# Bracelet_v3.net
KiCad netlist of a schematic drawn in EAGLE
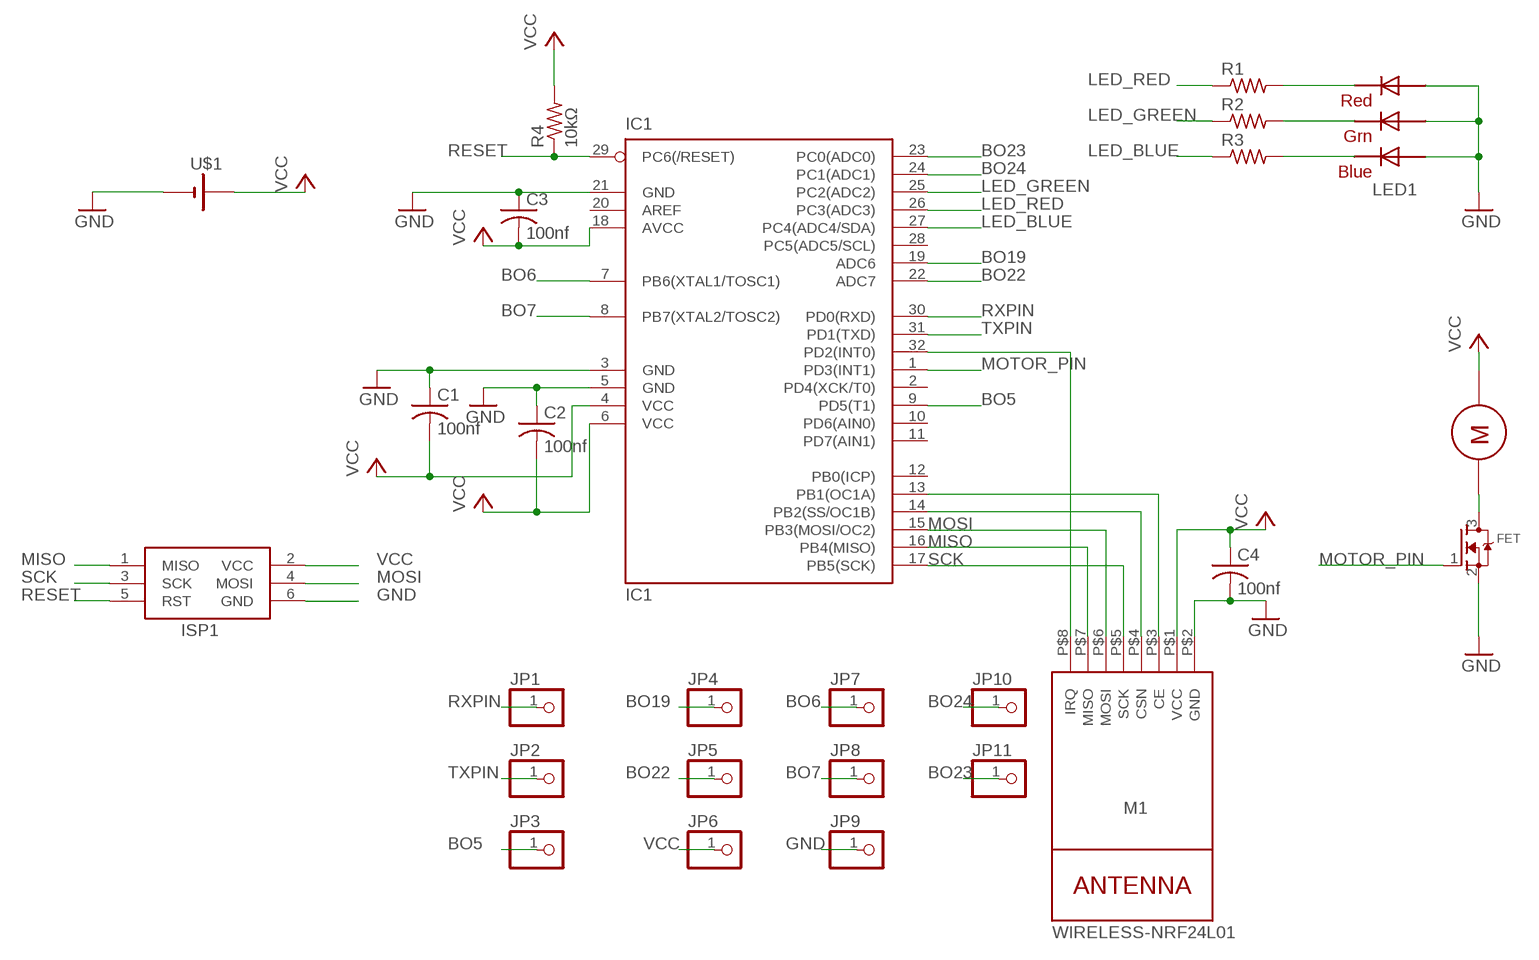
[diagram p0: schematic, sheet 1]

(export (version "E")
  (design (tool "Eeschema 10.0.6"))
  (components
    (comp (ref "C1")
      (value "100nf")
      (footprint "eagle-import:C0805")
      (libsource (lib "eagle-import") (part "resistor_C-USC0805"))
    )
    (comp (ref "C2")
      (value "100nf")
      (footprint "eagle-import:C0805")
      (libsource (lib "eagle-import") (part "C-USC0805"))
    )
    (comp (ref "C3")
      (value "100nf")
      (footprint "eagle-import:C0805")
      (libsource (lib "eagle-import") (part "resistor_C-USC0805"))
    )
    (comp (ref "C4")
      (value "100nf")
      (footprint "eagle-import:C0805")
      (libsource (lib "eagle-import") (part "C-USC0805"))
    )
    (comp (ref "FET")
      (value "MOSFET-NREFLOW")
      (footprint "eagle-import:SOT23")
      (libsource (lib "eagle-import") (part "MOSFET-NREFLOW"))
    )
    (comp (ref "IC1")
      (value "IC1")
      (footprint "eagle-import:TQFP32-08")
      (fields (field (name "MPN") "ATMEGA8-16AU"))
      (libsource (lib "eagle-import") (part "MEGA8-AI"))
    )
    (comp (ref "ISP1")
      (value "AVRISP-6")
      (footprint "eagle-import:AVRISP")
      (libsource (lib "eagle-import") (part "AVRISP-6"))
    )
    (comp (ref "JP1")
      (value "PINHD-1X1")
      (footprint "eagle-import:1X01")
      (libsource (lib "eagle-import") (part "PINHD-1X1"))
    )
    (comp (ref "JP2")
      (value "PINHD-1X1")
      (footprint "eagle-import:1X01")
      (libsource (lib "eagle-import") (part "PINHD-1X1"))
    )
    (comp (ref "JP3")
      (value "PINHD-1X1")
      (footprint "eagle-import:1X01")
      (libsource (lib "eagle-import") (part "PINHD-1X1"))
    )
    (comp (ref "JP4")
      (value "PINHD-1X1")
      (footprint "eagle-import:1X01")
      (libsource (lib "eagle-import") (part "PINHD-1X1"))
    )
    (comp (ref "JP5")
      (value "PINHD-1X1")
      (footprint "eagle-import:1X01")
      (libsource (lib "eagle-import") (part "PINHD-1X1"))
    )
    (comp (ref "JP6")
      (value "PINHD-1X1")
      (footprint "eagle-import:1X01")
      (libsource (lib "eagle-import") (part "PINHD-1X1"))
    )
    (comp (ref "JP7")
      (value "PINHD-1X1")
      (footprint "eagle-import:1X01")
      (libsource (lib "eagle-import") (part "PINHD-1X1"))
    )
    (comp (ref "JP8")
      (value "PINHD-1X1")
      (footprint "eagle-import:1X01")
      (libsource (lib "eagle-import") (part "PINHD-1X1"))
    )
    (comp (ref "JP9")
      (value "PINHD-1X1")
      (footprint "eagle-import:1X01")
      (libsource (lib "eagle-import") (part "PINHD-1X1"))
    )
    (comp (ref "JP10")
      (value "PINHD-1X1")
      (footprint "eagle-import:1X01")
      (libsource (lib "eagle-import") (part "PINHD-1X1"))
    )
    (comp (ref "JP11")
      (value "PINHD-1X1")
      (footprint "eagle-import:1X01")
      (libsource (lib "eagle-import") (part "PINHD-1X1"))
    )
    (comp (ref "LED1")
      (value "RGBLED5050")
      (footprint "eagle-import:RGBLED5050")
      (libsource (lib "eagle-import") (part "RGBLED5050"))
    )
    (comp (ref "M1")
      (value "WIRELESS-NRF24L01")
      (footprint "eagle-import:WIRELESS-NRF24L01")
      (libsource (lib "eagle-import") (part "WIRELESS-NRF24L01"))
    )
    (comp (ref "MOTOR")
      (value "Motor")
      (footprint "eagle-import:VIBRATING-MOTOR")
      (libsource (lib "eagle-import") (part "VIBRATING-MOTOR"))
    )
    (comp (ref "R1")
      (value "R-US_R0805")
      (footprint "eagle-import:R0805")
      (libsource (lib "eagle-import") (part "R-US_R0805"))
    )
    (comp (ref "R2")
      (value "R-US_R0805")
      (footprint "eagle-import:R0805")
      (libsource (lib "eagle-import") (part "R-US_R0805"))
    )
    (comp (ref "R3")
      (value "R-US_R0805")
      (footprint "eagle-import:R0805")
      (libsource (lib "eagle-import") (part "R-US_R0805"))
    )
    (comp (ref "R4")
      (value "10kΩ")
      (footprint "eagle-import:R0805")
      (libsource (lib "eagle-import") (part "R-US_R0805"))
    )
    (comp (ref "U$1")
      (value "CR2032SMT")
      (footprint "eagle-import:CR2032-SMD")
      (libsource (lib "eagle-import") (part "CR2032SMT"))
    )
  )
  (nets
    (net (code "1") (name "/BO5") (class "Default")
      (node (ref "IC1") (pin "9") (pinfunction "PD5(T1)_9") (pintype "bidirectional"))
      (node (ref "JP3") (pin "1") (pinfunction "1_1") (pintype "passive"))
    )
    (net (code "2") (name "/BO6") (class "Default")
      (node (ref "IC1") (pin "7") (pinfunction "PB6(XTAL1/TOSC1)_7") (pintype "bidirectional"))
      (node (ref "JP7") (pin "1") (pinfunction "1_1") (pintype "passive"))
    )
    (net (code "3") (name "/BO7") (class "Default")
      (node (ref "IC1") (pin "8") (pinfunction "PB7(XTAL2/TOSC2)_8") (pintype "bidirectional"))
      (node (ref "JP8") (pin "1") (pinfunction "1_1") (pintype "passive"))
    )
    (net (code "4") (name "/BO19") (class "Default")
      (node (ref "IC1") (pin "19") (pinfunction "ADC6_19") (pintype "bidirectional"))
      (node (ref "JP4") (pin "1") (pinfunction "1_1") (pintype "passive"))
    )
    (net (code "5") (name "/BO22") (class "Default")
      (node (ref "IC1") (pin "22") (pinfunction "ADC7_22") (pintype "bidirectional"))
      (node (ref "JP5") (pin "1") (pinfunction "1_1") (pintype "passive"))
    )
    (net (code "6") (name "/BO23") (class "Default")
      (node (ref "IC1") (pin "23") (pinfunction "PC0(ADC0)_23") (pintype "bidirectional"))
      (node (ref "JP11") (pin "1") (pinfunction "1_1") (pintype "passive"))
    )
    (net (code "7") (name "/BO24") (class "Default")
      (node (ref "IC1") (pin "24") (pinfunction "PC1(ADC1)_24") (pintype "bidirectional"))
      (node (ref "JP10") (pin "1") (pinfunction "1_1") (pintype "passive"))
    )
    (net (code "8") (name "/LED_BLUE") (class "Default")
      (node (ref "IC1") (pin "27") (pinfunction "PC4(ADC4/SDA)_27") (pintype "bidirectional"))
      (node (ref "R3") (pin "1") (pinfunction "1_1") (pintype "passive"))
    )
    (net (code "9") (name "/LED_GREEN") (class "Default")
      (node (ref "IC1") (pin "25") (pinfunction "PC2(ADC2)_25") (pintype "bidirectional"))
      (node (ref "R2") (pin "1") (pinfunction "1_1") (pintype "passive"))
    )
    (net (code "10") (name "/LED_RED") (class "Default")
      (node (ref "IC1") (pin "26") (pinfunction "PC3(ADC3)_26") (pintype "bidirectional"))
      (node (ref "R1") (pin "1") (pinfunction "1_1") (pintype "passive"))
    )
    (net (code "11") (name "/MISO") (class "Default")
      (node (ref "IC1") (pin "16") (pinfunction "PB4(MISO)_16") (pintype "bidirectional"))
      (node (ref "ISP1") (pin "1") (pinfunction "MISO_1") (pintype "input"))
      (node (ref "M1") (pin "P$7") (pinfunction "MISO_P$7") (pintype "bidirectional"))
    )
    (net (code "12") (name "/MOSI") (class "Default")
      (node (ref "IC1") (pin "15") (pinfunction "PB3(MOSI/OC2)_15") (pintype "bidirectional"))
      (node (ref "ISP1") (pin "4") (pinfunction "MOSI_4") (pintype "output"))
      (node (ref "M1") (pin "P$6") (pinfunction "MOSI_P$6") (pintype "bidirectional"))
    )
    (net (code "13") (name "/MOTOR_PIN") (class "Default")
      (node (ref "FET") (pin "1") (pinfunction "G_1") (pintype "bidirectional"))
      (node (ref "IC1") (pin "1") (pinfunction "PD3(INT1)_1") (pintype "bidirectional"))
    )
    (net (code "14") (name "/RESET") (class "Default")
      (node (ref "IC1") (pin "29") (pinfunction "PC6(/RESET)_29") (pintype "bidirectional"))
      (node (ref "ISP1") (pin "5") (pinfunction "RST_5") (pintype "output"))
      (node (ref "R4") (pin "1") (pinfunction "1_1") (pintype "passive"))
    )
    (net (code "15") (name "/RXPIN") (class "Default")
      (node (ref "IC1") (pin "30") (pinfunction "PD0(RXD)_30") (pintype "bidirectional"))
      (node (ref "JP1") (pin "1") (pinfunction "1_1") (pintype "passive"))
    )
    (net (code "16") (name "/SCK") (class "Default")
      (node (ref "IC1") (pin "17") (pinfunction "PB5(SCK)_17") (pintype "bidirectional"))
      (node (ref "ISP1") (pin "3") (pinfunction "SCK_3") (pintype "output"))
      (node (ref "M1") (pin "P$5") (pinfunction "SCK_P$5") (pintype "bidirectional"))
    )
    (net (code "17") (name "/TXPIN") (class "Default")
      (node (ref "IC1") (pin "31") (pinfunction "PD1(TXD)_31") (pintype "bidirectional"))
      (node (ref "JP2") (pin "1") (pinfunction "1_1") (pintype "passive"))
    )
    (net (code "18") (name "GND") (class "Default")
      (node (ref "C1") (pin "1") (pinfunction "1_1") (pintype "passive"))
      (node (ref "C2") (pin "1") (pinfunction "1_1") (pintype "passive"))
      (node (ref "C3") (pin "1") (pinfunction "1_1") (pintype "passive"))
      (node (ref "C4") (pin "2") (pinfunction "2_2") (pintype "passive"))
      (node (ref "FET") (pin "2") (pinfunction "S_2") (pintype "bidirectional"))
      (node (ref "IC1") (pin "21") (pinfunction "GND_21") (pintype "power_in"))
      (node (ref "IC1") (pin "3") (pinfunction "GND_3") (pintype "power_in"))
      (node (ref "IC1") (pin "5") (pinfunction "GND_5") (pintype "power_in"))
      (node (ref "ISP1") (pin "6") (pinfunction "GND_6") (pintype "power_in"))
      (node (ref "JP9") (pin "1") (pinfunction "1_1") (pintype "passive"))
      (node (ref "LED1") (pin "1") (pinfunction "GREEN_A_1") (pintype "bidirectional"))
      (node (ref "LED1") (pin "2") (pinfunction "RED_A_2") (pintype "bidirectional"))
      (node (ref "LED1") (pin "3") (pinfunction "BLUE_A_3") (pintype "bidirectional"))
      (node (ref "M1") (pin "P$2") (pinfunction "GND_P$2") (pintype "power_in"))
      (node (ref "U$1") (pin "-$1") (pinfunction "-_-$1") (pintype "passive"))
    )
    (net (code "19") (name "Net-(FET-D)") (class "Default")
      (node (ref "FET") (pin "3") (pinfunction "D_3") (pintype "bidirectional"))
      (node (ref "MOTOR") (pin "P$2") (pinfunction "P$2_P$2") (pintype "bidirectional"))
    )
    (net (code "20") (name "Net-(IC1-PB1(OC1A))") (class "Default")
      (node (ref "IC1") (pin "13") (pinfunction "PB1(OC1A)_13") (pintype "bidirectional"))
      (node (ref "M1") (pin "P$3") (pinfunction "CE_P$3") (pintype "bidirectional"))
    )
    (net (code "21") (name "Net-(IC1-PB2(SS{slash}OC1B))") (class "Default")
      (node (ref "IC1") (pin "14") (pinfunction "PB2(SS/OC1B)_14") (pintype "bidirectional"))
      (node (ref "M1") (pin "P$4") (pinfunction "CSN_P$4") (pintype "bidirectional"))
    )
    (net (code "22") (name "Net-(IC1-PD2(INT0))") (class "Default")
      (node (ref "IC1") (pin "32") (pinfunction "PD2(INT0)_32") (pintype "bidirectional"))
      (node (ref "M1") (pin "P$8") (pinfunction "IRQ_P$8") (pintype "bidirectional"))
    )
    (net (code "23") (name "Net-(LED1-BLUE_C)") (class "Default")
      (node (ref "LED1") (pin "4") (pinfunction "BLUE_C_4") (pintype "bidirectional"))
      (node (ref "R3") (pin "2") (pinfunction "2_2") (pintype "passive"))
    )
    (net (code "24") (name "Net-(LED1-GREEN_C)") (class "Default")
      (node (ref "LED1") (pin "6") (pinfunction "GREEN_C_6") (pintype "bidirectional"))
      (node (ref "R2") (pin "2") (pinfunction "2_2") (pintype "passive"))
    )
    (net (code "25") (name "Net-(LED1-RED_C)") (class "Default")
      (node (ref "LED1") (pin "5") (pinfunction "RED_C_5") (pintype "bidirectional"))
      (node (ref "R1") (pin "2") (pinfunction "2_2") (pintype "passive"))
    )
    (net (code "26") (name "VCC") (class "Default")
      (node (ref "C1") (pin "2") (pinfunction "2_2") (pintype "passive"))
      (node (ref "C2") (pin "2") (pinfunction "2_2") (pintype "passive"))
      (node (ref "C3") (pin "2") (pinfunction "2_2") (pintype "passive"))
      (node (ref "C4") (pin "1") (pinfunction "1_1") (pintype "passive"))
      (node (ref "IC1") (pin "18") (pinfunction "AVCC_18") (pintype "power_in"))
      (node (ref "IC1") (pin "4") (pinfunction "VCC_4") (pintype "power_in"))
      (node (ref "IC1") (pin "6") (pinfunction "VCC_6") (pintype "power_in"))
      (node (ref "ISP1") (pin "2") (pinfunction "VCC_2") (pintype "power_in"))
      (node (ref "JP6") (pin "1") (pinfunction "1_1") (pintype "passive"))
      (node (ref "M1") (pin "P$1") (pinfunction "VCC_P$1") (pintype "power_in"))
      (node (ref "MOTOR") (pin "NAME") (pinfunction "P$1_NAME") (pintype "bidirectional"))
      (node (ref "R4") (pin "2") (pinfunction "2_2") (pintype "passive"))
      (node (ref "U$1") (pin "+$1") (pinfunction "+1_+$1") (pintype "passive"))
    )
    (net (code "27") (name "unconnected-(IC1-AREF-Pad20)") (class "Default")
      (node (ref "IC1") (pin "20") (pinfunction "AREF_20") (pintype "passive"))
    )
    (net (code "28") (name "unconnected-(IC1-PB0(ICP)-Pad12)") (class "Default")
      (node (ref "IC1") (pin "12") (pinfunction "PB0(ICP)_12") (pintype "bidirectional"))
    )
    (net (code "29") (name "unconnected-(IC1-PC5(ADC5{slash}SCL)-Pad28)") (class "Default")
      (node (ref "IC1") (pin "28") (pinfunction "PC5(ADC5/SCL)_28") (pintype "bidirectional"))
    )
    (net (code "30") (name "unconnected-(IC1-PD4(XCK{slash}T0)-Pad2)") (class "Default")
      (node (ref "IC1") (pin "2") (pinfunction "PD4(XCK/T0)_2") (pintype "bidirectional"))
    )
    (net (code "31") (name "unconnected-(IC1-PD6(AIN0)-Pad10)") (class "Default")
      (node (ref "IC1") (pin "10") (pinfunction "PD6(AIN0)_10") (pintype "bidirectional"))
    )
    (net (code "32") (name "unconnected-(IC1-PD7(AIN1)-Pad11)") (class "Default")
      (node (ref "IC1") (pin "11") (pinfunction "PD7(AIN1)_11") (pintype "bidirectional"))
    )
  )
)
